# CON_VIDEO_OUT.net
KiCad netlist of a schematic drawn in Altium Designer
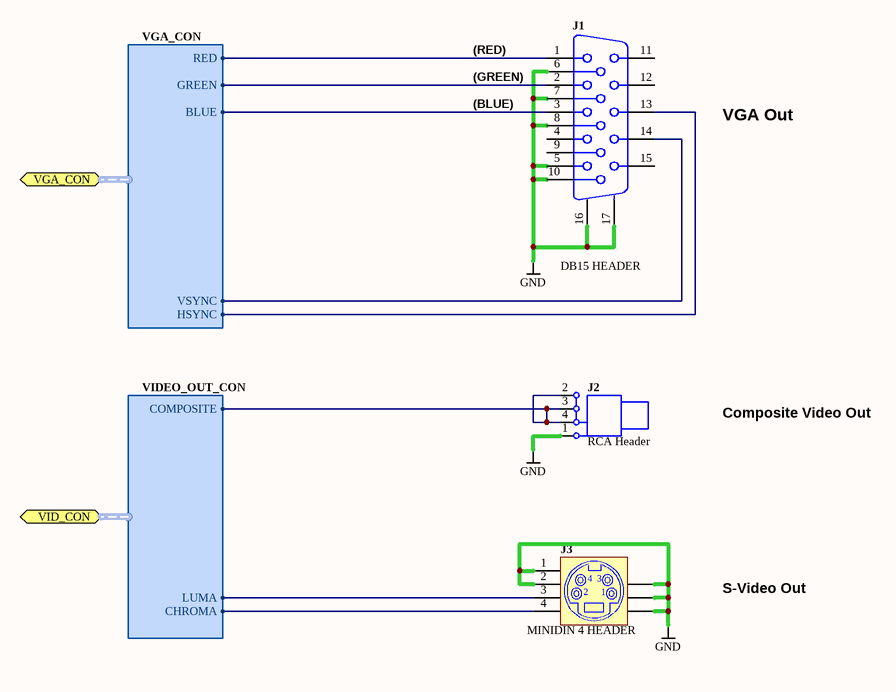
[diagram p0: CON_VIDEO_OUT.SchDoc]

(export (version "E")
  (design (tool "Eeschema 10.0.6"))
  (components
    (comp (ref "J1")
      (value "DB15 HEADER")
      (footprint "DB15-VGA-Female")
      (description "Connector, DB15 Right-Angle Female (Analog RGB Video)/Blue")
      (libsource (lib "AltiumDesignLibrary") (part "CON-DB-15-F-RA"))
    )
    (comp (ref "J2")
      (value "RCA Header")
      (footprint "TRC-005")
      (description "Connector, TRC-005-4 , RCA Phono Jack, Right Angle, Thru-Hole, Snap-In")
      (libsource (lib "AltiumDesignLibrary") (part "CON-RCA-RA"))
    )
    (comp (ref "J3")
      (value "MINIDIN 4 HEADER")
      (footprint "MDJ-F-04")
      (description "Connector, 4850.241, Mini-DIN 4-Way, S-Video/Yellow")
      (libsource (lib "AltiumDesignLibrary") (part "CON-MINIDIN-4-F"))
    )
  )
  (nets
    (net (code "3") (name "/BLUE") (class "Default")
      (node (ref "J1") (pin "3") (pinfunction "3_3") (pintype "passive"))
    )
    (net (code "4") (name "/CHROMA") (class "Default")
      (node (ref "J3") (pin "4") (pinfunction "E_4") (pintype "passive"))
    )
    (net (code "5") (name "/COMPOSITE") (class "Default")
      (node (ref "J2") (pin "2") (pinfunction "Yellow_2") (pintype "passive"))
      (node (ref "J2") (pin "3") (pinfunction "White_3") (pintype "passive"))
      (node (ref "J2") (pin "4") (pinfunction "Red_4") (pintype "passive"))
    )
    (net (code "6") (name "/GREEN") (class "Default")
      (node (ref "J1") (pin "2") (pinfunction "2_2") (pintype "passive"))
    )
    (net (code "7") (name "/HSYNC") (class "Default")
      (node (ref "J1") (pin "13") (pinfunction "13_13") (pintype "passive"))
    )
    (net (code "8") (name "/LUMA") (class "Default")
      (node (ref "J3") (pin "3") (pinfunction "H_3") (pintype "passive"))
    )
    (net (code "9") (name "/RED") (class "Default")
      (node (ref "J1") (pin "1") (pinfunction "1_1") (pintype "passive"))
    )
    (net (code "10") (name "/VSYNC") (class "Default")
      (node (ref "J1") (pin "14") (pinfunction "14_14") (pintype "passive"))
    )
    (net (code "13") (name "GND") (class "Default")
      (node (ref "J1") (pin "10") (pinfunction "10_10") (pintype "power_in"))
      (node (ref "J1") (pin "16") (pinfunction "MH1_16") (pintype "passive"))
      (node (ref "J1") (pin "17") (pinfunction "MH2_17") (pintype "passive"))
      (node (ref "J1") (pin "5") (pinfunction "5_5") (pintype "power_in"))
      (node (ref "J1") (pin "6") (pinfunction "6_6") (pintype "power_in"))
      (node (ref "J1") (pin "7") (pinfunction "7_7") (pintype "power_in"))
      (node (ref "J1") (pin "8") (pinfunction "8_8") (pintype "power_in"))
      (node (ref "J2") (pin "1") (pinfunction "Black_1") (pintype "passive"))
      (node (ref "J3") (pin "1") (pinfunction "D_1") (pintype "passive"))
      (node (ref "J3") (pin "2") (pinfunction "A_2") (pintype "passive"))
      (node (ref "J3") (pin "MH1") (pinfunction "MH1_MH1") (pintype "passive"))
      (node (ref "J3") (pin "MH2") (pinfunction "MH2_MH2") (pintype "passive"))
      (node (ref "J3") (pin "MH3") (pinfunction "MH3_MH3") (pintype "passive"))
    )
    (net (code "14") (name "unconnected-(J1-Pad4)") (class "Default")
      (node (ref "J1") (pin "4") (pinfunction "4_4") (pintype "passive"))
    )
    (net (code "15") (name "unconnected-(J1-Pad9)") (class "Default")
      (node (ref "J1") (pin "9") (pinfunction "9_9") (pintype "passive"))
    )
    (net (code "16") (name "unconnected-(J1-Pad11)") (class "Default")
      (node (ref "J1") (pin "11") (pinfunction "11_11") (pintype "power_in"))
    )
    (net (code "17") (name "unconnected-(J1-Pad12)") (class "Default")
      (node (ref "J1") (pin "12") (pinfunction "12_12") (pintype "passive"))
    )
    (net (code "18") (name "unconnected-(J1-Pad15)") (class "Default")
      (node (ref "J1") (pin "15") (pinfunction "15_15") (pintype "passive"))
    )
  )
)
